# BMS.net
KiCad netlist of a schematic drawn in Altium Designer
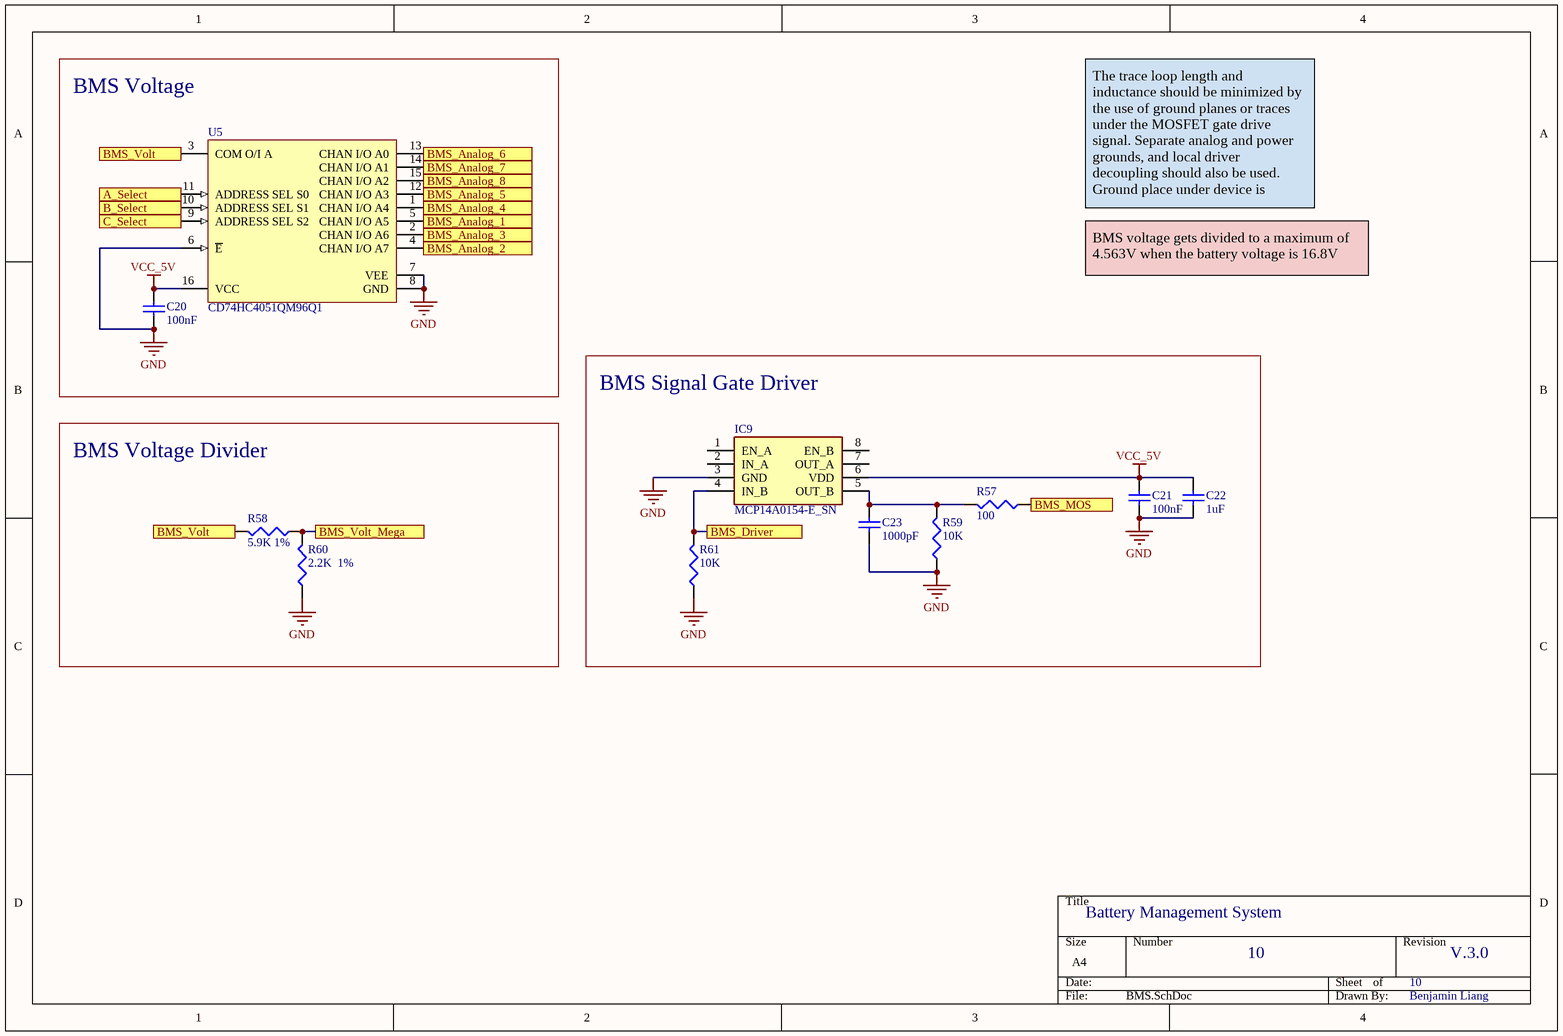
[diagram p0: BMS.SchDoc]

(export (version "E")
  (design (tool "Eeschema 10.0.6"))
  (components
    (comp (ref "C20")
      (value "100nF")
      (footprint "C1206")
      (description "Capacitor (Semiconductor SIM Model)")
      (fields (field (name "PUBLISHER") "Altium Limited"))
      (libsource (lib "Miscellaneous Devices") (part "Cap Semi"))
    )
    (comp (ref "C21")
      (value "100nF")
      (footprint "C1206")
      (description "Capacitor (Semiconductor SIM Model)")
      (fields (field (name "PUBLISHER") "Altium Limited"))
      (libsource (lib "Miscellaneous Devices") (part "Cap Semi"))
    )
    (comp (ref "C22")
      (value "1uF")
      (footprint "C1206")
      (description "Capacitor (Semiconductor SIM Model)")
      (fields (field (name "PUBLISHER") "Altium Limited"))
      (libsource (lib "Miscellaneous Devices") (part "Cap Semi"))
    )
    (comp (ref "C23")
      (value "1000pF")
      (footprint "C1206")
      (description "Capacitor (Semiconductor SIM Model)")
      (fields (field (name "PUBLISHER") "Altium Limited"))
      (libsource (lib "Miscellaneous Devices") (part "Cap Semi"))
    )
    (comp (ref "IC9")
      (value "MCP14A0154-E_SN")
      (footprint "SOIC127P599X173-8N")
      (description "Integrated Circuit")
      (fields
        (field (name "MANUFACTURER_PART_NUMBER") "MCP14A0154-E/SN")
        (field (name "MOUSER PART NUMBER") "579-MCP14A0154-E/SN")
      )
      (libsource (lib "*") (part "MCP14A0154-E_SN"))
    )
    (comp (ref "R57")
      (value "100")
      (footprint "J1-0603")
      (description "Resistor")
      (fields (field (name "PUBLISHER") "Altium Limited"))
      (libsource (lib "Miscellaneous Devices") (part "Res3"))
    )
    (comp (ref "R58")
      (value "5.9K 1%")
      (footprint "J1-0603")
      (description "Resistor")
      (fields (field (name "PUBLISHER") "Altium Limited"))
      (libsource (lib "Miscellaneous Devices") (part "Res3"))
    )
    (comp (ref "R59")
      (value "10K")
      (footprint "J1-0603")
      (description "Resistor")
      (fields (field (name "PUBLISHER") "Altium Limited"))
      (libsource (lib "Miscellaneous Devices") (part "Res3"))
    )
    (comp (ref "R60")
      (value "2.2K  1%")
      (footprint "J1-0603")
      (description "Resistor")
      (fields (field (name "PUBLISHER") "Altium Limited"))
      (libsource (lib "Miscellaneous Devices") (part "Res3"))
    )
    (comp (ref "R61")
      (value "10K")
      (footprint "J1-0603")
      (description "Resistor")
      (fields (field (name "PUBLISHER") "Altium Limited"))
      (libsource (lib "Miscellaneous Devices") (part "Res3"))
    )
    (comp (ref "U5")
      (value "CD74HC4051QM96Q1")
      (footprint "D0016A_L")
      (description "Automotive Catalog High Speed CMOS Logic Analog Multiplexers/Demultiplexers, D0016A, LARGE T&R")
      (fields
        (field (name "GENERIC PART NUMBER") "CD74HC4051-Q1")
        (field (name "MANUFACTURER") "Texas Instruments")
      )
      (libsource (lib "Altium Content Vault") (part "TI-CD74HC4051-Q1-D0016A-16"))
    )
  )
  (nets
    (net (code "1") (name "/A_Select") (class "Default")
      (node (ref "U5") (pin "11") (pinfunction "ADDRESS_SEL_S0_11") (pintype "input"))
    )
    (net (code "2") (name "/BMS_Analog_1") (class "Default")
      (node (ref "U5") (pin "5") (pinfunction "CHAN_I/O_A5_5") (pintype "passive"))
    )
    (net (code "3") (name "/BMS_Analog_2") (class "Default")
      (node (ref "U5") (pin "4") (pinfunction "CHAN_I/O_A7_4") (pintype "passive"))
    )
    (net (code "4") (name "/BMS_Analog_3") (class "Default")
      (node (ref "U5") (pin "2") (pinfunction "CHAN_I/O_A6_2") (pintype "passive"))
    )
    (net (code "5") (name "/BMS_Analog_4") (class "Default")
      (node (ref "U5") (pin "1") (pinfunction "CHAN_I/O_A4_1") (pintype "passive"))
    )
    (net (code "6") (name "/BMS_Analog_5") (class "Default")
      (node (ref "U5") (pin "12") (pinfunction "CHAN_I/O_A3_12") (pintype "passive"))
    )
    (net (code "7") (name "/BMS_Analog_6") (class "Default")
      (node (ref "U5") (pin "13") (pinfunction "CHAN_I/O_A0_13") (pintype "passive"))
    )
    (net (code "8") (name "/BMS_Analog_7") (class "Default")
      (node (ref "U5") (pin "14") (pinfunction "CHAN_I/O_A1_14") (pintype "passive"))
    )
    (net (code "9") (name "/BMS_Analog_8") (class "Default")
      (node (ref "U5") (pin "15") (pinfunction "CHAN_I/O_A2_15") (pintype "passive"))
    )
    (net (code "10") (name "/BMS_Driver") (class "Default")
      (node (ref "IC9") (pin "4") (pinfunction "IN_B_4") (pintype "passive"))
      (node (ref "R61") (pin "2") (pinfunction "2_2") (pintype "passive"))
    )
    (net (code "11") (name "/BMS_MOS") (class "Default")
      (node (ref "R57") (pin "1") (pinfunction "1_1") (pintype "passive"))
    )
    (net (code "12") (name "/BMS_Volt") (class "Default")
      (node (ref "R58") (pin "2") (pinfunction "2_2") (pintype "passive"))
      (node (ref "U5") (pin "3") (pinfunction "COM_O/I_A_3") (pintype "passive"))
    )
    (net (code "13") (name "/BMS_Volt_Mega") (class "Default")
      (node (ref "R58") (pin "1") (pinfunction "1_1") (pintype "passive"))
      (node (ref "R60") (pin "2") (pinfunction "2_2") (pintype "passive"))
    )
    (net (code "14") (name "/B_Select") (class "Default")
      (node (ref "U5") (pin "10") (pinfunction "ADDRESS_SEL_S1_10") (pintype "input"))
    )
    (net (code "15") (name "/C_Select") (class "Default")
      (node (ref "U5") (pin "9") (pinfunction "ADDRESS_SEL_S2_9") (pintype "input"))
    )
    (net (code "16") (name "GND") (class "Default")
      (node (ref "C20") (pin "2") (pinfunction "2_2") (pintype "passive"))
      (node (ref "C21") (pin "2") (pinfunction "2_2") (pintype "passive"))
      (node (ref "C22") (pin "2") (pinfunction "2_2") (pintype "passive"))
      (node (ref "C23") (pin "2") (pinfunction "2_2") (pintype "passive"))
      (node (ref "IC9") (pin "3") (pinfunction "GND_3") (pintype "passive"))
      (node (ref "R59") (pin "1") (pinfunction "1_1") (pintype "passive"))
      (node (ref "R60") (pin "1") (pinfunction "1_1") (pintype "passive"))
      (node (ref "R61") (pin "1") (pinfunction "1_1") (pintype "passive"))
      (node (ref "U5") (pin "6") (pinfunction "~{E}_6") (pintype "input"))
      (node (ref "U5") (pin "7") (pinfunction "VEE_7") (pintype "power_in"))
      (node (ref "U5") (pin "8") (pinfunction "GND_8") (pintype "power_in"))
    )
    (net (code "17") (name "Net-(IC9-OUT_B)") (class "Default")
      (node (ref "C23") (pin "1") (pinfunction "1_1") (pintype "passive"))
      (node (ref "IC9") (pin "5") (pinfunction "OUT_B_5") (pintype "passive"))
      (node (ref "R57") (pin "2") (pinfunction "2_2") (pintype "passive"))
      (node (ref "R59") (pin "2") (pinfunction "2_2") (pintype "passive"))
    )
    (net (code "18") (name "VCC_5V") (class "Default")
      (node (ref "C20") (pin "1") (pinfunction "1_1") (pintype "passive"))
      (node (ref "C21") (pin "1") (pinfunction "1_1") (pintype "passive"))
      (node (ref "C22") (pin "1") (pinfunction "1_1") (pintype "passive"))
      (node (ref "IC9") (pin "6") (pinfunction "VDD_6") (pintype "passive"))
      (node (ref "U5") (pin "16") (pinfunction "VCC_16") (pintype "power_in"))
    )
    (net (code "19") (name "unconnected-(IC9-EN_A-Pad1)") (class "Default")
      (node (ref "IC9") (pin "1") (pinfunction "EN_A_1") (pintype "passive"))
    )
    (net (code "20") (name "unconnected-(IC9-EN_B-Pad8)") (class "Default")
      (node (ref "IC9") (pin "8") (pinfunction "EN_B_8") (pintype "passive"))
    )
    (net (code "21") (name "unconnected-(IC9-IN_A-Pad2)") (class "Default")
      (node (ref "IC9") (pin "2") (pinfunction "IN_A_2") (pintype "passive"))
    )
    (net (code "22") (name "unconnected-(IC9-OUT_A-Pad7)") (class "Default")
      (node (ref "IC9") (pin "7") (pinfunction "OUT_A_7") (pintype "passive"))
    )
  )
)
